# akabeacon_circle_da14580.net
KiCad netlist of a schematic drawn in EAGLE
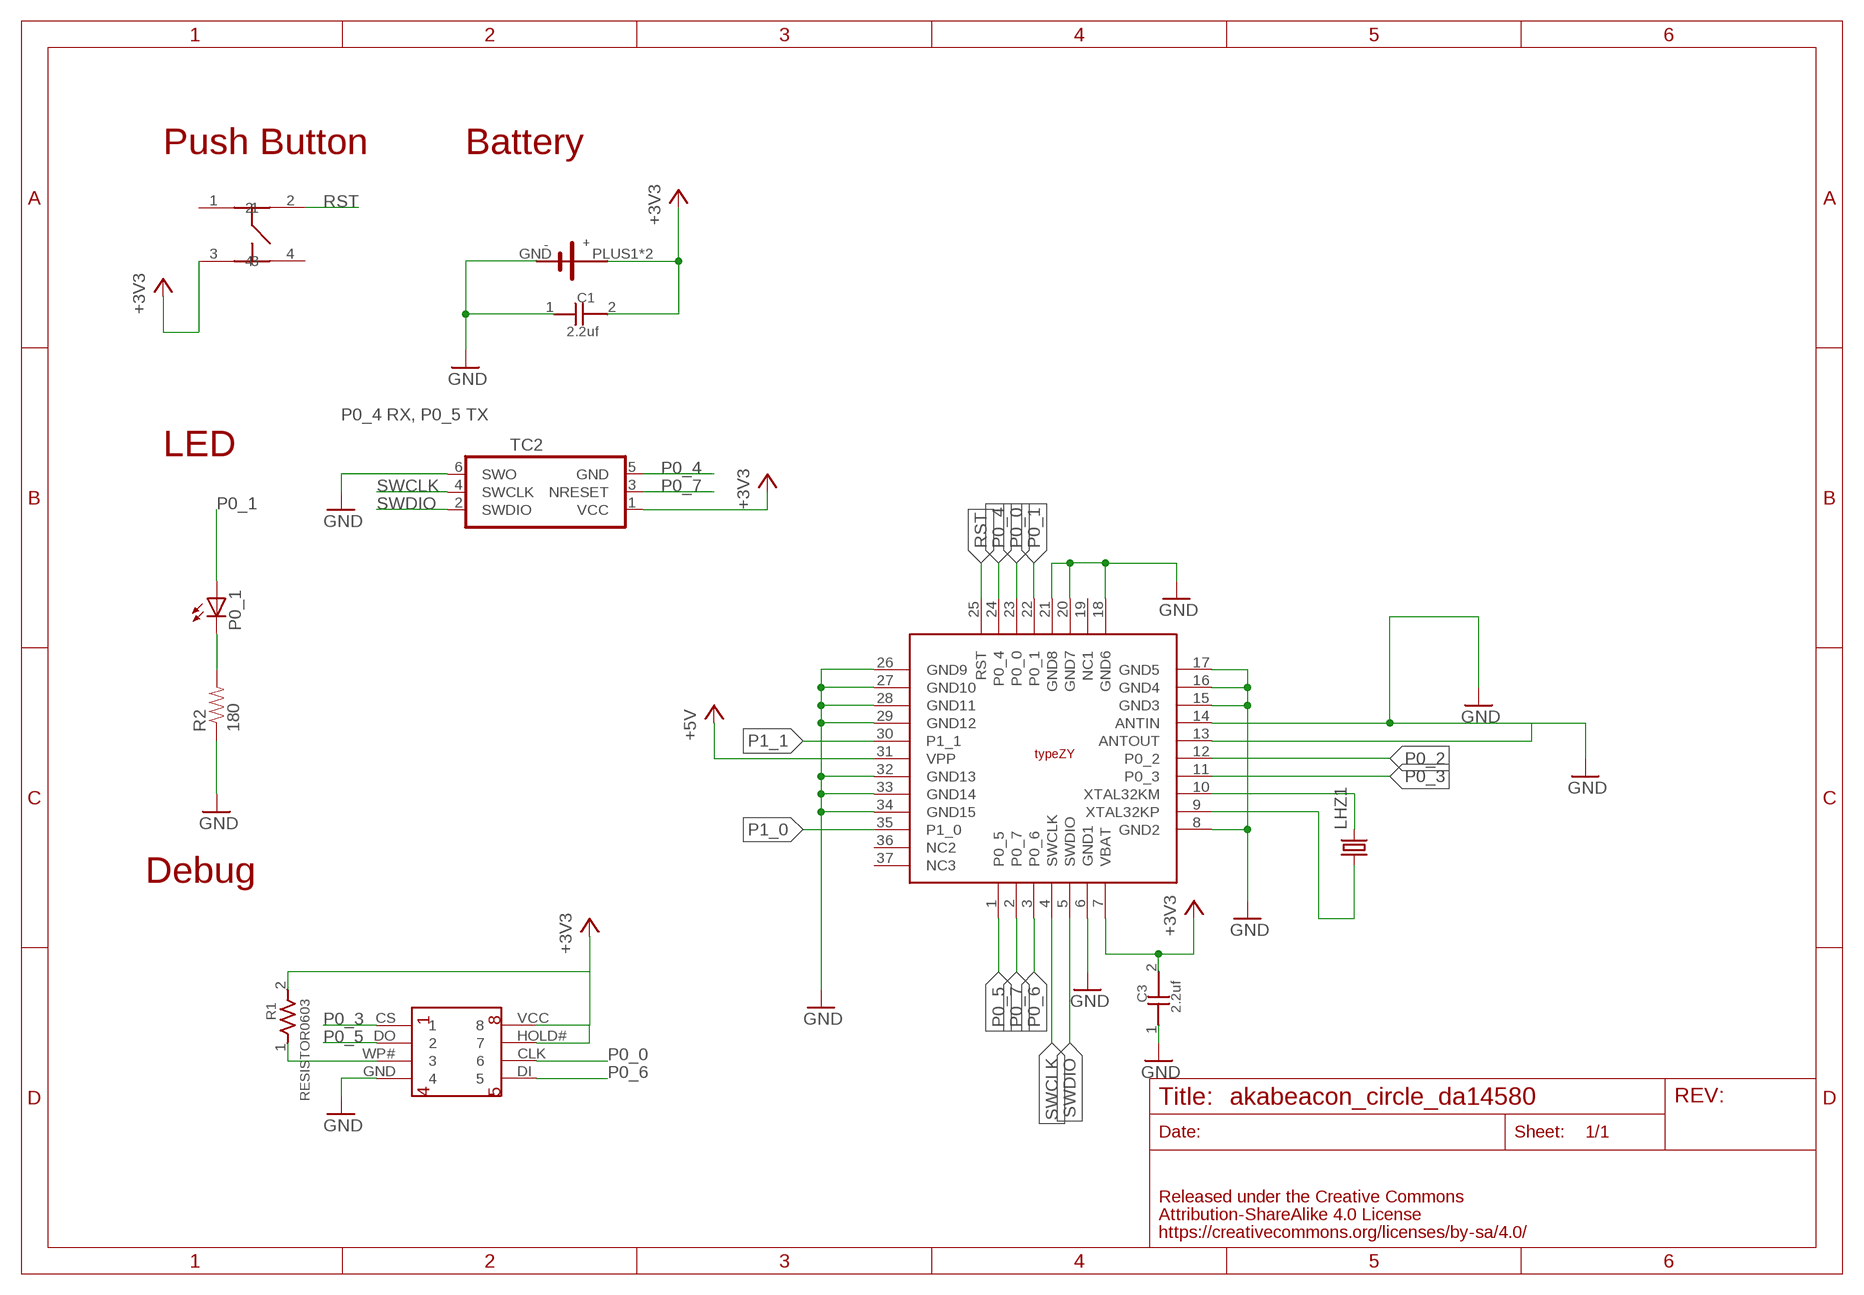
[diagram p0: schematic, sheet 1]

(export (version "E")
  (design (tool "Eeschema 10.0.6"))
  (components
    (comp (ref "C1")
      (value "2.2uf")
      (footprint "eagle-import:0603")
      (libsource (lib "eagle-import") (part "CAPACITOR0603"))
    )
    (comp (ref "C3")
      (value "2.2uf")
      (footprint "eagle-import:0603")
      (libsource (lib "eagle-import") (part "CAPACITOR0603"))
    )
    (comp (ref "LHZ1")
      (value "FC-12M")
      (footprint "eagle-import:FC-12M")
      (libsource (lib "eagle-import") (part "FC-12M"))
    )
    (comp (ref "P0_1")
      (value "LEDCHIP-LED0603")
      (footprint "eagle-import:CHIP-LED0603")
      (libsource (lib "eagle-import") (part "LEDCHIP-LED0603"))
    )
    (comp (ref "R1")
      (value "RESISTOR0603")
      (footprint "eagle-import:0603")
      (libsource (lib "eagle-import") (part "RESISTOR0603"))
    )
    (comp (ref "R2")
      (value "180")
      (footprint "eagle-import:0603-RES")
      (libsource (lib "eagle-import") (part "RESISTOR0603-RES"))
    )
    (comp (ref "TC2")
      (value "TC2030-IDC-NL")
      (footprint "eagle-import:TC2030-IDC-NL")
      (libsource (lib "eagle-import") (part "TC2030-IDC-NL"))
    )
    (comp (ref "U$1")
      (value "MURATA-TYPEZY")
      (footprint "eagle-import:MURATA_TYPEZY")
      (libsource (lib "eagle-import") (part "MURATA-TYPEZY"))
    )
    (comp (ref "U$3")
      (value "CIRCLE-TYPE1")
      (footprint "eagle-import:CIRCLE-TYE1-TC2030")
      (libsource (lib "eagle-import") (part "CIRCLE-TYPE1"))
    )
    (comp (ref "U$5")
      (value "FLASH-MEMORY-2M(WINBOND)")
      (footprint "eagle-import:FLASH-MEMORY-2M(WINBOND)")
      (libsource (lib "eagle-import") (part "FLASH-MEMORY-2M(WINBOND)"))
    )
    (comp (ref "U$7")
      (value "SWICTH-4P(KMR2)")
      (footprint "eagle-import:SWITCH-4P(KMR2)")
      (libsource (lib "eagle-import") (part "SWICTH-4P(KMR2)"))
    )
  )
  (nets
    (net (code "1") (name "+3V3") (class "Default")
      (node (ref "C1") (pin "2") (pinfunction "2_2") (pintype "passive"))
      (node (ref "C3") (pin "2") (pinfunction "2_2") (pintype "passive"))
      (node (ref "R1") (pin "2") (pinfunction "2_2") (pintype "passive"))
      (node (ref "TC2") (pin "1") (pinfunction "VCC_1") (pintype "passive"))
      (node (ref "U$1") (pin "7") (pinfunction "VBAT_7") (pintype "bidirectional"))
      (node (ref "U$3") (pin "PLUS1") (pinfunction "VCC_PLUS1") (pintype "bidirectional"))
      (node (ref "U$3") (pin "PLUS2") (pinfunction "VCC_PLUS2") (pintype "bidirectional"))
      (node (ref "U$5") (pin "HOLD#") (pinfunction "7_HOLD#") (pintype "bidirectional"))
      (node (ref "U$5") (pin "VCC") (pinfunction "8_VCC") (pintype "bidirectional"))
      (node (ref "U$7") (pin "3") (pinfunction "3_3") (pintype "bidirectional"))
    )
    (net (code "2") (name "+5V") (class "Default")
      (node (ref "U$1") (pin "31") (pinfunction "VPP_31") (pintype "bidirectional"))
    )
    (net (code "3") (name "GND") (class "Default")
      (node (ref "C1") (pin "1") (pinfunction "1_1") (pintype "passive"))
      (node (ref "C3") (pin "1") (pinfunction "1_1") (pintype "passive"))
      (node (ref "R2") (pin "1") (pinfunction "1_1") (pintype "passive"))
      (node (ref "TC2") (pin "6") (pinfunction "SWO_6") (pintype "passive"))
      (node (ref "U$1") (pin "14") (pinfunction "ANTIN_14") (pintype "bidirectional"))
      (node (ref "U$1") (pin "15") (pinfunction "GND3_15") (pintype "bidirectional"))
      (node (ref "U$1") (pin "16") (pinfunction "GND4_16") (pintype "bidirectional"))
      (node (ref "U$1") (pin "17") (pinfunction "GND5_17") (pintype "bidirectional"))
      (node (ref "U$1") (pin "18") (pinfunction "GND6_18") (pintype "bidirectional"))
      (node (ref "U$1") (pin "20") (pinfunction "GND7_20") (pintype "bidirectional"))
      (node (ref "U$1") (pin "21") (pinfunction "GND8_21") (pintype "bidirectional"))
      (node (ref "U$1") (pin "26") (pinfunction "GND9_26") (pintype "bidirectional"))
      (node (ref "U$1") (pin "27") (pinfunction "GND10_27") (pintype "bidirectional"))
      (node (ref "U$1") (pin "28") (pinfunction "GND11_28") (pintype "bidirectional"))
      (node (ref "U$1") (pin "29") (pinfunction "GND12_29") (pintype "bidirectional"))
      (node (ref "U$1") (pin "32") (pinfunction "GND13_32") (pintype "bidirectional"))
      (node (ref "U$1") (pin "33") (pinfunction "GND14_33") (pintype "bidirectional"))
      (node (ref "U$1") (pin "34") (pinfunction "GND15_34") (pintype "bidirectional"))
      (node (ref "U$1") (pin "6") (pinfunction "GND1_6") (pintype "bidirectional"))
      (node (ref "U$1") (pin "8") (pinfunction "GND2_8") (pintype "bidirectional"))
      (node (ref "U$3") (pin "GND") (pinfunction "GND_GND") (pintype "bidirectional"))
      (node (ref "U$5") (pin "GND") (pinfunction "4_GND") (pintype "bidirectional"))
    )
    (net (code "4") (name "Net-(P0_1-PadC)") (class "Default")
      (node (ref "P0_1") (pin "C") (pinfunction "C_C") (pintype "passive"))
      (node (ref "R2") (pin "2") (pinfunction "2_2") (pintype "passive"))
    )
    (net (code "5") (name "Net-(U$1-XTAL32KM)") (class "Default")
      (node (ref "LHZ1") (pin "2") (pinfunction "2_2") (pintype "passive"))
      (node (ref "U$1") (pin "10") (pinfunction "XTAL32KM_10") (pintype "bidirectional"))
    )
    (net (code "6") (name "Net-(U$1-XTAL32KP)") (class "Default")
      (node (ref "LHZ1") (pin "1") (pinfunction "1_1") (pintype "passive"))
      (node (ref "U$1") (pin "9") (pinfunction "XTAL32KP_9") (pintype "bidirectional"))
    )
    (net (code "7") (name "Net-(U$5-3)") (class "Default")
      (node (ref "R1") (pin "1") (pinfunction "1_1") (pintype "passive"))
      (node (ref "U$5") (pin "WP#") (pinfunction "3_WP#") (pintype "bidirectional"))
    )
    (net (code "8") (name "P0_0") (class "Default")
      (node (ref "U$1") (pin "23") (pinfunction "P0_0_23") (pintype "bidirectional"))
      (node (ref "U$5") (pin "CLK") (pinfunction "6_CLK") (pintype "bidirectional"))
    )
    (net (code "9") (name "P0_1") (class "Default")
      (node (ref "P0_1") (pin "A") (pinfunction "A_A") (pintype "passive"))
      (node (ref "U$1") (pin "22") (pinfunction "P0_1_22") (pintype "bidirectional"))
    )
    (net (code "10") (name "P0_2") (class "Default")
      (node (ref "U$1") (pin "12") (pinfunction "P0_2_12") (pintype "bidirectional"))
    )
    (net (code "11") (name "P0_3") (class "Default")
      (node (ref "U$1") (pin "11") (pinfunction "P0_3_11") (pintype "bidirectional"))
      (node (ref "U$5") (pin "CS") (pinfunction "1_CS") (pintype "bidirectional"))
    )
    (net (code "12") (name "P0_4") (class "Default")
      (node (ref "TC2") (pin "5") (pinfunction "GND_5") (pintype "passive"))
      (node (ref "U$1") (pin "24") (pinfunction "P0_4_24") (pintype "bidirectional"))
    )
    (net (code "13") (name "P0_5") (class "Default")
      (node (ref "U$1") (pin "1") (pinfunction "P0_5_1") (pintype "bidirectional"))
      (node (ref "U$5") (pin "DO") (pinfunction "2_DO") (pintype "bidirectional"))
    )
    (net (code "14") (name "P0_6") (class "Default")
      (node (ref "U$1") (pin "3") (pinfunction "P0_6_3") (pintype "bidirectional"))
      (node (ref "U$5") (pin "DI") (pinfunction "5_DI") (pintype "bidirectional"))
    )
    (net (code "15") (name "P0_7") (class "Default")
      (node (ref "TC2") (pin "3") (pinfunction "NRESET_3") (pintype "passive"))
      (node (ref "U$1") (pin "2") (pinfunction "P0_7_2") (pintype "bidirectional"))
    )
    (net (code "16") (name "P1_0") (class "Default")
      (node (ref "U$1") (pin "35") (pinfunction "P1_0_35") (pintype "bidirectional"))
    )
    (net (code "17") (name "P1_1") (class "Default")
      (node (ref "U$1") (pin "30") (pinfunction "P1_1_30") (pintype "bidirectional"))
    )
    (net (code "18") (name "RST") (class "Default")
      (node (ref "U$1") (pin "25") (pinfunction "RST_25") (pintype "bidirectional"))
      (node (ref "U$7") (pin "2") (pinfunction "2_2") (pintype "bidirectional"))
    )
    (net (code "19") (name "SWCLK") (class "Default")
      (node (ref "TC2") (pin "4") (pinfunction "SWCLK_4") (pintype "passive"))
      (node (ref "U$1") (pin "4") (pinfunction "SWCLK_4") (pintype "bidirectional"))
    )
    (net (code "20") (name "SWDIO") (class "Default")
      (node (ref "TC2") (pin "2") (pinfunction "SWDIO_2") (pintype "passive"))
      (node (ref "U$1") (pin "5") (pinfunction "SWDIO_5") (pintype "bidirectional"))
    )
    (net (code "21") (name "unconnected-(U$1-ANTOUT-Pad13)") (class "Default")
      (node (ref "U$1") (pin "13") (pinfunction "ANTOUT_13") (pintype "bidirectional"))
    )
    (net (code "22") (name "unconnected-(U$1-NC1-Pad19)") (class "Default")
      (node (ref "U$1") (pin "19") (pinfunction "NC1_19") (pintype "bidirectional"))
    )
    (net (code "23") (name "unconnected-(U$1-NC2-Pad36)") (class "Default")
      (node (ref "U$1") (pin "36") (pinfunction "NC2_36") (pintype "bidirectional"))
    )
    (net (code "24") (name "unconnected-(U$1-NC3-Pad37)") (class "Default")
      (node (ref "U$1") (pin "37") (pinfunction "NC3_37") (pintype "bidirectional"))
    )
    (net (code "25") (name "unconnected-(U$7-Pad1)") (class "Default")
      (node (ref "U$7") (pin "1") (pinfunction "1_1") (pintype "bidirectional"))
    )
    (net (code "26") (name "unconnected-(U$7-Pad4)") (class "Default")
      (node (ref "U$7") (pin "4") (pinfunction "4_4") (pintype "bidirectional"))
    )
  )
)
